# DM1097_AV.net
KiCad netlist of a schematic drawn in Altium Designer
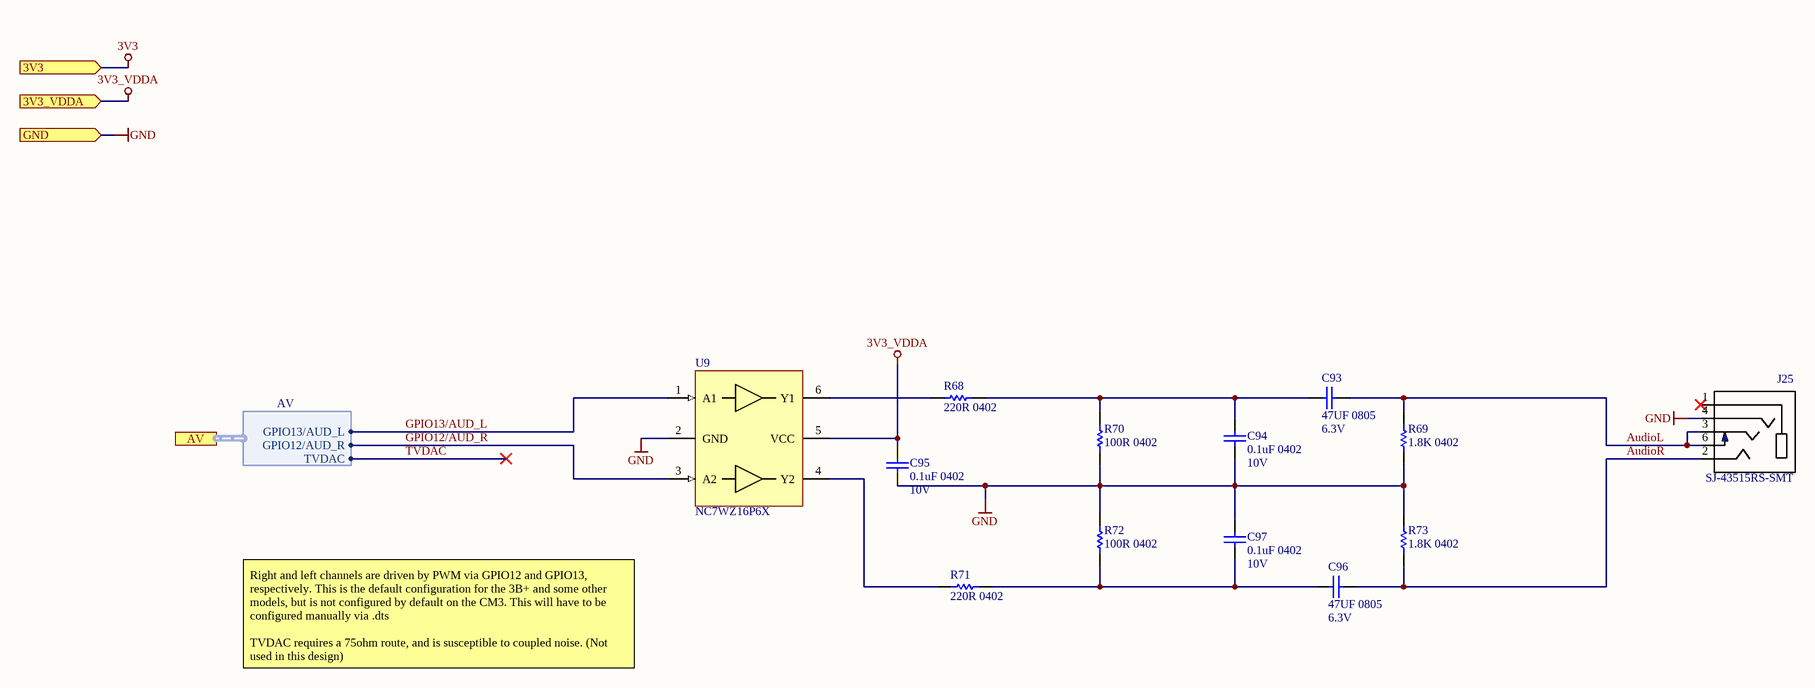
[diagram p0: DM1097_AV.SchDoc]

(export (version "E")
  (design (tool "Eeschema 10.0.6"))
  (components
    (comp (ref "C93")
      (value "47UF 0805")
      (footprint "CAP_Altium_Vault_Generic:CAPC0805(2012)145_N")
      (description "CAP CER 47UF 6.3V X5R 0805")
      (fields (field (name "TOLERANCE") "20%") (field (name "VOLTAGE") "6.3V"))
      (libsource (lib "LuxonisMaster") (part "GRM21BR60J476ME15L"))
    )
    (comp (ref "C94")
      (value "0.1uF 0402")
      (footprint "CAP_Altium_Vault_Generic:CAPC0402(1005)70_N")
      (description "CAP CER 0.1UF 10V X7R 0402 5%")
      (fields (field (name "TOLERANCE") "5%") (field (name "VOLTAGE RATING") "10V"))
      (libsource (lib "LuxonisMaster") (part "GRM155R71A104JA01D"))
    )
    (comp (ref "C95")
      (value "0.1uF 0402")
      (footprint "CAP_Altium_Vault_Generic:CAPC0402(1005)70_N")
      (description "CAP CER 0.1UF 10V X7R 0402 5%")
      (fields (field (name "TOLERANCE") "5%") (field (name "VOLTAGE RATING") "10V"))
      (libsource (lib "LuxonisMaster") (part "GRM155R71A104JA01D"))
    )
    (comp (ref "C96")
      (value "47UF 0805")
      (footprint "CAP_Altium_Vault_Generic:CAPC0805(2012)145_N")
      (description "CAP CER 47UF 6.3V X5R 0805")
      (fields (field (name "TOLERANCE") "20%") (field (name "VOLTAGE") "6.3V"))
      (libsource (lib "LuxonisMaster") (part "GRM21BR60J476ME15L"))
    )
    (comp (ref "C97")
      (value "0.1uF 0402")
      (footprint "CAP_Altium_Vault_Generic:CAPC0402(1005)70_N")
      (description "CAP CER 0.1UF 10V X7R 0402 5%")
      (fields (field (name "TOLERANCE") "5%") (field (name "VOLTAGE RATING") "10V"))
      (libsource (lib "LuxonisMaster") (part "GRM155R71A104JA01D"))
    )
    (comp (ref "J25")
      (value "SJ-43515RS-SMT")
      (footprint "LuxonisMaster:SJ-43515RS-SMT")
      (description "CONN JACK 4COND 3.5MM SMD R/A")
      (libsource (lib "LuxonisMaster") (part "SJ-43515RS-SMT"))
    )
    (comp (ref "R68")
      (value "220R 0402")
      (footprint "RES_Altium_Vault_Generic:RESC0402(1005)_N")
      (description "RES SMD 220 OHM 1% 1/16W 0402")
      (fields (field (name "TOLERANCE") "1%"))
      (libsource (lib "LuxonisMaster") (part "RC0402FR-07220RL"))
    )
    (comp (ref "R69")
      (value "1.8K 0402")
      (footprint "RES_Altium_Vault_Generic:RESC0402(1005)_N")
      (description "RES SMD 1.8K OHM 1% 1/16W 0402")
      (fields (field (name "TOLERANCE") "1%"))
      (libsource (lib "LuxonisMaster") (part "RC0402FR-071K8L"))
    )
    (comp (ref "R70")
      (value "100R 0402")
      (footprint "RES_Altium_Vault_Generic:RESC0402(1005)_N")
      (description "RES SMD 100 OHM 1% 1/16W 0402")
      (fields (field (name "TOLERANCE") "1%"))
      (libsource (lib "LuxonisMaster") (part "RC0402FR-07100RL"))
    )
    (comp (ref "R71")
      (value "220R 0402")
      (footprint "RES_Altium_Vault_Generic:RESC0402(1005)_N")
      (description "RES SMD 220 OHM 1% 1/16W 0402")
      (fields (field (name "TOLERANCE") "1%"))
      (libsource (lib "LuxonisMaster") (part "RC0402FR-07220RL"))
    )
    (comp (ref "R72")
      (value "100R 0402")
      (footprint "RES_Altium_Vault_Generic:RESC0402(1005)_N")
      (description "RES SMD 100 OHM 1% 1/16W 0402")
      (fields (field (name "TOLERANCE") "1%"))
      (libsource (lib "LuxonisMaster") (part "RC0402FR-07100RL"))
    )
    (comp (ref "R73")
      (value "1.8K 0402")
      (footprint "RES_Altium_Vault_Generic:RESC0402(1005)_N")
      (description "RES SMD 1.8K OHM 1% 1/16W 0402")
      (fields (field (name "TOLERANCE") "1%"))
      (libsource (lib "LuxonisMaster") (part "RC0402FR-071K8L"))
    )
    (comp (ref "U9")
      (value "NC7WZ16P6X")
      (footprint "LuxonisMaster:NC7WZ16P6X")
      (libsource (lib "LuxonisMaster") (part "NC7WZ16P6X"))
    )
  )
  (nets
    (net (code "2") (name "/AudioL") (class "Default")
      (node (ref "C93") (pin "1") (pinfunction "1_1") (pintype "passive"))
      (node (ref "J25") (pin "3") (pinfunction "RING1_3") (pintype "passive"))
      (node (ref "J25") (pin "6") (pinfunction "RING_SWITCH_6") (pintype "passive"))
      (node (ref "R69") (pin "2") (pinfunction "2_2") (pintype "passive"))
    )
    (net (code "3") (name "/AudioR") (class "Default")
      (node (ref "C96") (pin "1") (pinfunction "1_1") (pintype "passive"))
      (node (ref "J25") (pin "2") (pinfunction "TIP_2") (pintype "passive"))
      (node (ref "R73") (pin "2") (pinfunction "2_2") (pintype "passive"))
    )
    (net (code "4") (name "/GPIO12{slash}AUD_R") (class "Default")
      (node (ref "U9") (pin "3") (pinfunction "A2_3") (pintype "input"))
    )
    (net (code "5") (name "/GPIO13{slash}AUD_L") (class "Default")
      (node (ref "U9") (pin "1") (pinfunction "A1_1") (pintype "input"))
    )
    (net (code "9") (name "3V3_VDDA") (class "Default")
      (node (ref "C95") (pin "2") (pinfunction "2_2") (pintype "passive"))
      (node (ref "U9") (pin "5") (pinfunction "VCC_5") (pintype "power_in"))
    )
    (net (code "10") (name "GND") (class "Default")
      (node (ref "C94") (pin "1") (pinfunction "1_1") (pintype "passive"))
      (node (ref "C95") (pin "1") (pinfunction "1_1") (pintype "passive"))
      (node (ref "C97") (pin "1") (pinfunction "1_1") (pintype "passive"))
      (node (ref "J25") (pin "4") (pinfunction "RING2_4") (pintype "passive"))
      (node (ref "R69") (pin "1") (pinfunction "1_1") (pintype "passive"))
      (node (ref "R70") (pin "1") (pinfunction "1_1") (pintype "passive"))
      (node (ref "R72") (pin "1") (pinfunction "1_1") (pintype "passive"))
      (node (ref "R73") (pin "1") (pinfunction "1_1") (pintype "passive"))
      (node (ref "U9") (pin "2") (pinfunction "GND_2") (pintype "power_in"))
    )
    (net (code "11") (name "Net-(C93-Pad2)") (class "Default")
      (node (ref "C93") (pin "2") (pinfunction "2_2") (pintype "passive"))
      (node (ref "C94") (pin "2") (pinfunction "2_2") (pintype "passive"))
      (node (ref "R68") (pin "2") (pinfunction "2_2") (pintype "passive"))
      (node (ref "R70") (pin "2") (pinfunction "2_2") (pintype "passive"))
    )
    (net (code "12") (name "Net-(C96-Pad2)") (class "Default")
      (node (ref "C96") (pin "2") (pinfunction "2_2") (pintype "passive"))
      (node (ref "C97") (pin "2") (pinfunction "2_2") (pintype "passive"))
      (node (ref "R71") (pin "2") (pinfunction "2_2") (pintype "passive"))
      (node (ref "R72") (pin "2") (pinfunction "2_2") (pintype "passive"))
    )
    (net (code "13") (name "Net-(U9-Y1)") (class "Default")
      (node (ref "R68") (pin "1") (pinfunction "1_1") (pintype "passive"))
      (node (ref "U9") (pin "6") (pinfunction "Y1_6") (pintype "open_collector"))
    )
    (net (code "14") (name "Net-(U9-Y2)") (class "Default")
      (node (ref "R71") (pin "1") (pinfunction "1_1") (pintype "passive"))
      (node (ref "U9") (pin "4") (pinfunction "Y2_4") (pintype "open_collector"))
    )
    (net (code "15") (name "unconnected-(J25-SLEEVE-Pad1)") (class "Default")
      (node (ref "J25") (pin "1") (pinfunction "SLEEVE_1") (pintype "passive+no_connect"))
    )
  )
)
